# BBConnector.net
KiCad netlist of a schematic drawn in EAGLE
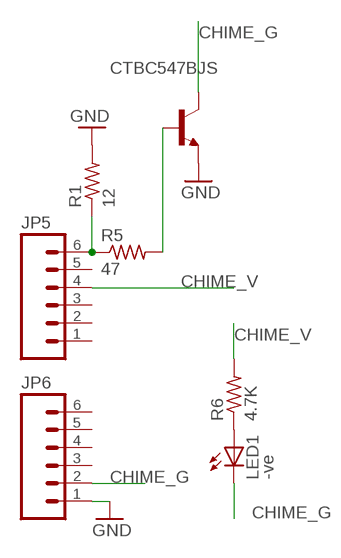
[diagram p0: schematic, sheet 1]

(export (version "E")
  (design (tool "Eeschema 10.0.6"))
  (components
    (comp (ref "CTBC547BJS")
      (value "2N2222")
      (footprint "eagle-import:TO92-EBC-OVAL")
      (libsource (lib "eagle-import") (part "2N2222"))
    )
    (comp (ref "JP5")
      (value "M06NO_SILK_YES_STOP")
      (footprint "eagle-import:1X06_NO_SILK_YES_STOP")
      (libsource (lib "eagle-import") (part "M06NO_SILK_YES_STOP"))
    )
    (comp (ref "JP6")
      (value "M06NO_SILK_YES_STOP")
      (footprint "eagle-import:1X06_NO_SILK_YES_STOP")
      (libsource (lib "eagle-import") (part "M06NO_SILK_YES_STOP"))
    )
    (comp (ref "LED1")
      (value "-ve")
      (footprint "eagle-import:CHIP-LED0603")
      (libsource (lib "eagle-import") (part "LEDCHIP-LED0603"))
    )
    (comp (ref "R1")
      (value "12")
      (footprint "eagle-import:R0603")
      (libsource (lib "eagle-import") (part "R-US_R0603"))
    )
    (comp (ref "R5")
      (value "47")
      (footprint "eagle-import:R0603")
      (libsource (lib "eagle-import") (part "R-US_R0603"))
    )
    (comp (ref "R6")
      (value "4.7K")
      (footprint "eagle-import:R0603")
      (libsource (lib "eagle-import") (part "R-US_R0603"))
    )
  )
  (nets
    (net (code "1") (name "/CHIME_G") (class "Default")
      (node (ref "CTBC547BJS") (pin "C") (pinfunction "C_C") (pintype "passive"))
      (node (ref "JP6") (pin "2") (pinfunction "2_2") (pintype "passive"))
      (node (ref "LED1") (pin "C") (pinfunction "C_C") (pintype "passive"))
    )
    (net (code "2") (name "/CHIME_V") (class "Default")
      (node (ref "JP5") (pin "4") (pinfunction "4_4") (pintype "passive"))
      (node (ref "R6") (pin "2") (pinfunction "2_2") (pintype "passive"))
    )
    (net (code "3") (name "GND") (class "Default")
      (node (ref "CTBC547BJS") (pin "E") (pinfunction "E_E") (pintype "passive"))
      (node (ref "JP6") (pin "1") (pinfunction "1_1") (pintype "passive"))
      (node (ref "R1") (pin "2") (pinfunction "2_2") (pintype "passive"))
    )
    (net (code "4") (name "Net-(CTBC547BJS-PadB)") (class "Default")
      (node (ref "CTBC547BJS") (pin "B") (pinfunction "B_B") (pintype "passive"))
      (node (ref "R5") (pin "2") (pinfunction "2_2") (pintype "passive"))
    )
    (net (code "5") (name "Net-(JP5-Pad6)") (class "Default")
      (node (ref "JP5") (pin "6") (pinfunction "6_6") (pintype "passive"))
      (node (ref "R1") (pin "1") (pinfunction "1_1") (pintype "passive"))
      (node (ref "R5") (pin "1") (pinfunction "1_1") (pintype "passive"))
    )
    (net (code "6") (name "Net-(LED1-PadA)") (class "Default")
      (node (ref "LED1") (pin "A") (pinfunction "A_A") (pintype "passive"))
      (node (ref "R6") (pin "1") (pinfunction "1_1") (pintype "passive"))
    )
    (net (code "7") (name "unconnected-(JP5-Pad1)") (class "Default")
      (node (ref "JP5") (pin "1") (pinfunction "1_1") (pintype "passive"))
    )
    (net (code "8") (name "unconnected-(JP5-Pad2)") (class "Default")
      (node (ref "JP5") (pin "2") (pinfunction "2_2") (pintype "passive"))
    )
    (net (code "9") (name "unconnected-(JP5-Pad3)") (class "Default")
      (node (ref "JP5") (pin "3") (pinfunction "3_3") (pintype "passive"))
    )
    (net (code "10") (name "unconnected-(JP5-Pad5)") (class "Default")
      (node (ref "JP5") (pin "5") (pinfunction "5_5") (pintype "passive"))
    )
    (net (code "11") (name "unconnected-(JP6-Pad3)") (class "Default")
      (node (ref "JP6") (pin "3") (pinfunction "3_3") (pintype "passive"))
    )
    (net (code "12") (name "unconnected-(JP6-Pad4)") (class "Default")
      (node (ref "JP6") (pin "4") (pinfunction "4_4") (pintype "passive"))
    )
    (net (code "13") (name "unconnected-(JP6-Pad5)") (class "Default")
      (node (ref "JP6") (pin "5") (pinfunction "5_5") (pintype "passive"))
    )
    (net (code "14") (name "unconnected-(JP6-Pad6)") (class "Default")
      (node (ref "JP6") (pin "6") (pinfunction "6_6") (pintype "passive"))
    )
  )
)
